# RS232_NPN_PNP_4Pin_Conn_Rev_Alt.net
KiCad netlist of a schematic drawn in EAGLE
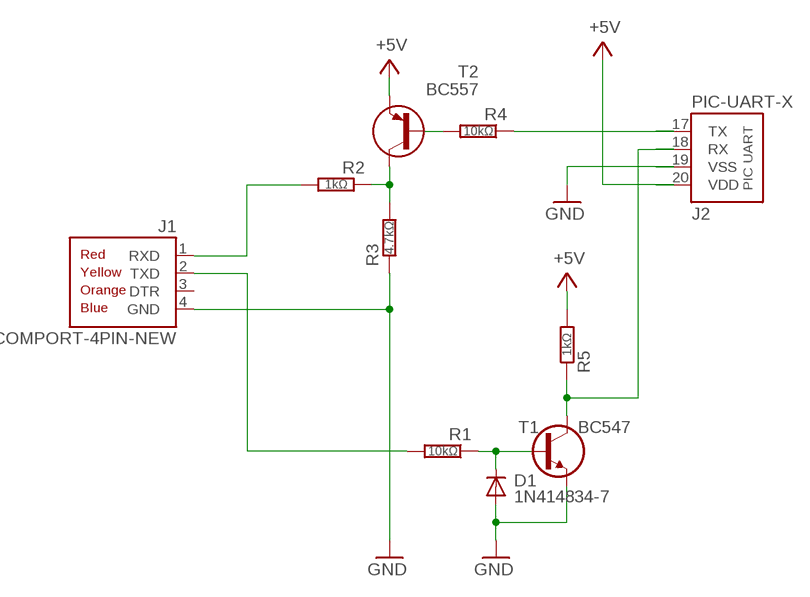
[diagram p0: schematic, sheet 1]

(export (version "E")
  (design (tool "Eeschema 10.0.6"))
  (components
    (comp (ref "D1")
      (value "1N414834-7")
      (footprint "eagle-import:DO34-7")
      (libsource (lib "eagle-import") (part "1N414834-7"))
    )
    (comp (ref "J1")
      (value "COMPORT-4PIN-NEW")
      (footprint "eagle-import:RS232-4PIN-NEW")
      (libsource (lib "eagle-import") (part "COMPORT-4PIN-NEW"))
    )
    (comp (ref "J2")
      (value "PIC-UART-X")
      (footprint "eagle-import:PIC-UART-X")
      (libsource (lib "eagle-import") (part "PIC-UART-X"))
    )
    (comp (ref "R1")
      (value "10kΩ")
      (footprint "eagle-import:0202_7")
      (libsource (lib "eagle-import") (part "R0202/7"))
    )
    (comp (ref "R2")
      (value "1kΩ")
      (footprint "eagle-import:0202_7")
      (libsource (lib "eagle-import") (part "R0202/7"))
    )
    (comp (ref "R3")
      (value "4.7kΩ")
      (footprint "eagle-import:0202_7")
      (libsource (lib "eagle-import") (part "R0202/7"))
    )
    (comp (ref "R4")
      (value "10kΩ")
      (footprint "eagle-import:0202_7-V")
      (libsource (lib "eagle-import") (part "R0202/7-V"))
    )
    (comp (ref "R5")
      (value "1kΩ")
      (footprint "eagle-import:0202_7-V")
      (libsource (lib "eagle-import") (part "R0202/7-V"))
    )
    (comp (ref "T1")
      (value "BC547")
      (footprint "eagle-import:TO92-CBE")
      (libsource (lib "eagle-import") (part "BC547CBE"))
    )
    (comp (ref "T2")
      (value "BC557")
      (footprint "eagle-import:TO92-CBE")
      (libsource (lib "eagle-import") (part "BC557CBE"))
    )
  )
  (nets
    (net (code "1") (name "+5V") (class "Default")
      (node (ref "J2") (pin "20") (pinfunction "VDD_20") (pintype "passive"))
      (node (ref "R5") (pin "2") (pinfunction "2_2") (pintype "passive"))
      (node (ref "T2") (pin "E") (pinfunction "E_E") (pintype "passive"))
    )
    (net (code "2") (name "GND") (class "Default")
      (node (ref "D1") (pin "A") (pinfunction "A_A") (pintype "passive"))
      (node (ref "J1") (pin "4") (pinfunction "GND_4") (pintype "passive"))
      (node (ref "J2") (pin "19") (pinfunction "VSS_19") (pintype "passive"))
      (node (ref "R3") (pin "1") (pinfunction "1_1") (pintype "passive"))
      (node (ref "T1") (pin "E") (pinfunction "E_E") (pintype "passive"))
    )
    (net (code "3") (name "Net-(D1-PadC)") (class "Default")
      (node (ref "D1") (pin "C") (pinfunction "C_C") (pintype "passive"))
      (node (ref "R1") (pin "1") (pinfunction "1_1") (pintype "passive"))
      (node (ref "T1") (pin "B") (pinfunction "B_B") (pintype "passive"))
    )
    (net (code "4") (name "Net-(J1-RXD)") (class "Default")
      (node (ref "J1") (pin "1") (pinfunction "RXD_1") (pintype "passive"))
      (node (ref "R2") (pin "2") (pinfunction "2_2") (pintype "passive"))
    )
    (net (code "5") (name "Net-(J1-TXD)") (class "Default")
      (node (ref "J1") (pin "2") (pinfunction "TXD_2") (pintype "passive"))
      (node (ref "R1") (pin "2") (pinfunction "2_2") (pintype "passive"))
    )
    (net (code "6") (name "Net-(J2-RX)") (class "Default")
      (node (ref "J2") (pin "18") (pinfunction "RX_18") (pintype "passive"))
      (node (ref "R5") (pin "1") (pinfunction "1_1") (pintype "passive"))
      (node (ref "T1") (pin "C") (pinfunction "C_C") (pintype "passive"))
    )
    (net (code "7") (name "Net-(J2-TX)") (class "Default")
      (node (ref "J2") (pin "17") (pinfunction "TX_17") (pintype "passive"))
      (node (ref "R4") (pin "1") (pinfunction "1_1") (pintype "passive"))
    )
    (net (code "8") (name "Net-(R2-Pad1)") (class "Default")
      (node (ref "R2") (pin "1") (pinfunction "1_1") (pintype "passive"))
      (node (ref "R3") (pin "2") (pinfunction "2_2") (pintype "passive"))
      (node (ref "T2") (pin "C") (pinfunction "C_C") (pintype "passive"))
    )
    (net (code "9") (name "Net-(R4-Pad2)") (class "Default")
      (node (ref "R4") (pin "2") (pinfunction "2_2") (pintype "passive"))
      (node (ref "T2") (pin "B") (pinfunction "B_B") (pintype "passive"))
    )
    (net (code "10") (name "unconnected-(J1-DTR-Pad3)") (class "Default")
      (node (ref "J1") (pin "3") (pinfunction "DTR_3") (pintype "passive"))
    )
  )
)
